# Sheet1.net
KiCad netlist of a schematic drawn in Altium Designer
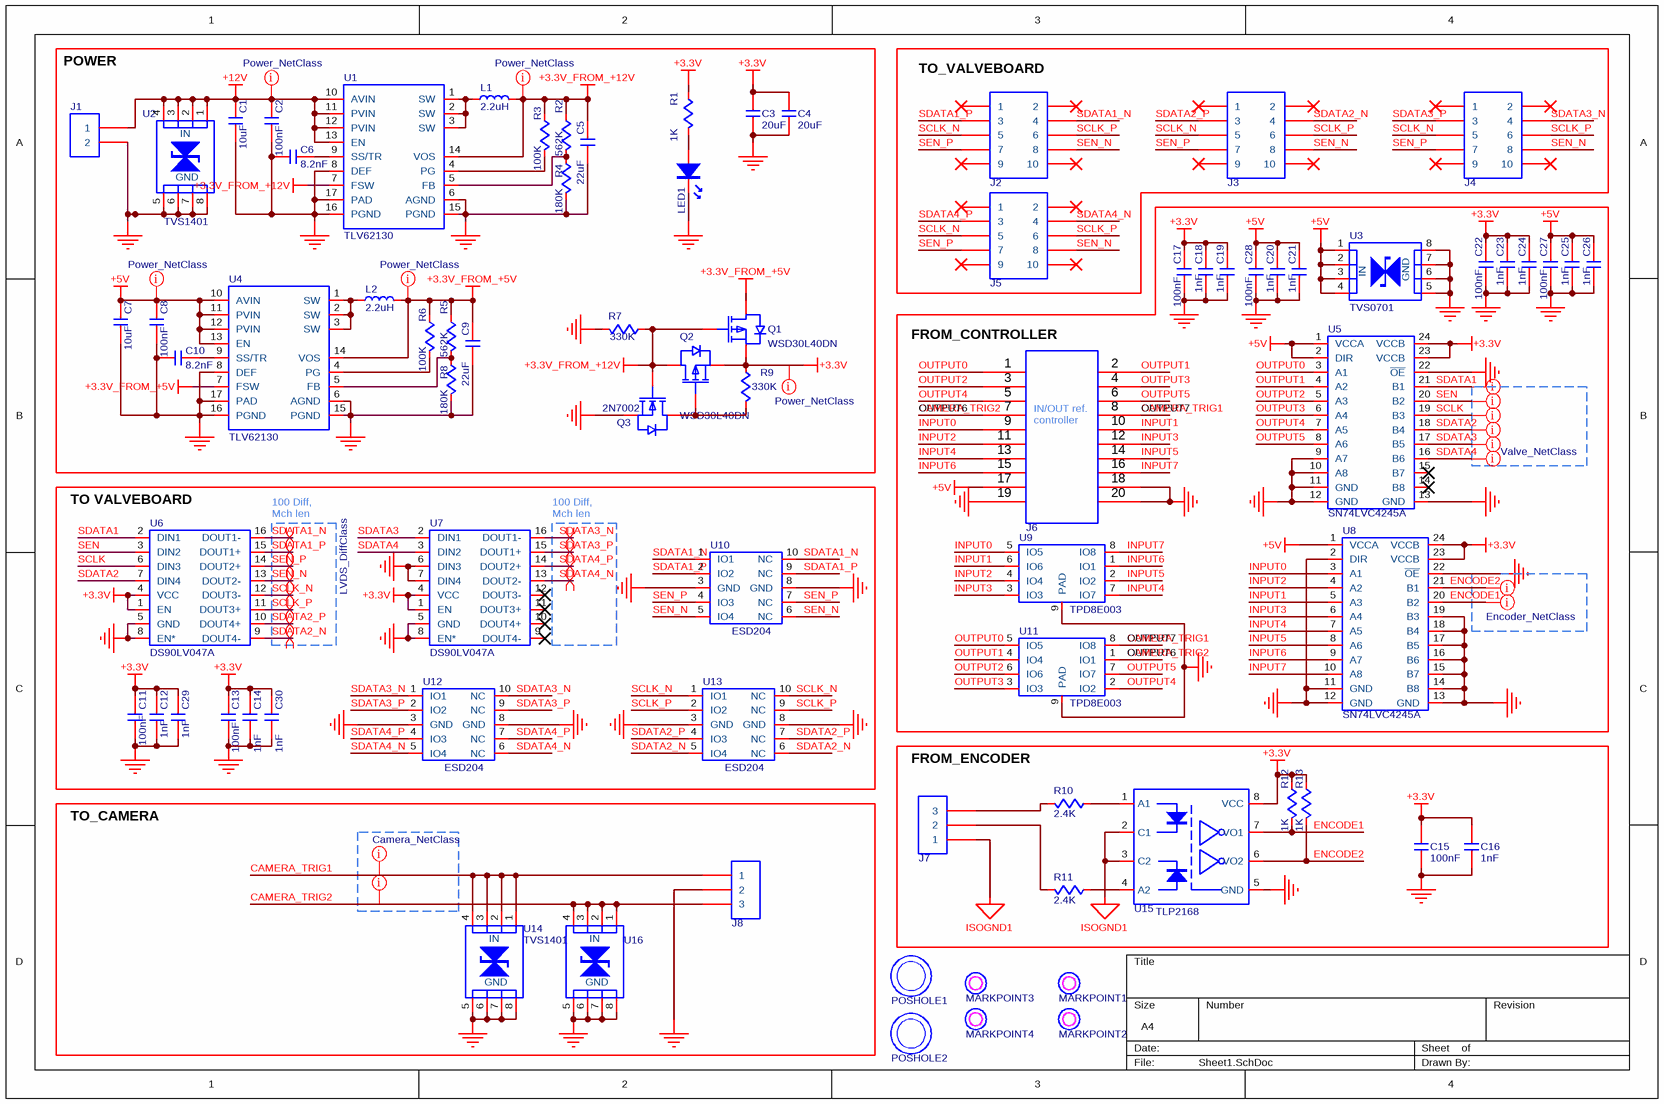
[diagram p0: Sheet1.SchDoc]

(export (version "E")
  (design (tool "Eeschema 10.0.6"))
  (components
    (comp (ref "C1")
      (value "10uF")
      (footprint "mw:C0805")
      (fields (field (name "VOLTAGE") "25V") (field (name "Comment") "C-NOMO"))
      (libsource (lib "mw") (part "C-NOMO"))
    )
    (comp (ref "C2")
      (value "100nF")
      (footprint "mw:C0402")
      (fields (field (name "VOLTAGE") "25V") (field (name "Comment") "C-NOMO"))
      (libsource (lib "mw") (part "C-NOMO"))
    )
    (comp (ref "C3")
      (value "20uF")
      (footprint "mw:C0805")
      (fields (field (name "VOLTAGE") "25V") (field (name "Comment") "C-NOMO"))
      (libsource (lib "mw") (part "C-NOMO"))
    )
    (comp (ref "C4")
      (value "20uF")
      (footprint "mw:C0805")
      (fields (field (name "VOLTAGE") "25V") (field (name "Comment") "C-NOMO"))
      (libsource (lib "mw") (part "C-NOMO"))
    )
    (comp (ref "C5")
      (value "22uF")
      (footprint "mw:C0805")
      (fields (field (name "VOLTAGE") "25V") (field (name "Comment") "C-NOMO"))
      (libsource (lib "mw") (part "C-NOMO"))
    )
    (comp (ref "C6")
      (value "8.2nF")
      (footprint "mw:C0402")
      (fields (field (name "VOLTAGE") "25V") (field (name "Comment") "C-NOMO"))
      (libsource (lib "mw") (part "C-NOMO"))
    )
    (comp (ref "C7")
      (value "10uF")
      (footprint "mw:C0805")
      (fields (field (name "VOLTAGE") "25V") (field (name "Comment") "C-NOMO"))
      (libsource (lib "mw") (part "C-NOMO"))
    )
    (comp (ref "C8")
      (value "100nF")
      (footprint "mw:C0402")
      (fields (field (name "VOLTAGE") "25V") (field (name "Comment") "C-NOMO"))
      (libsource (lib "mw") (part "C-NOMO"))
    )
    (comp (ref "C9")
      (value "22uF")
      (footprint "mw:C0805")
      (fields (field (name "VOLTAGE") "25V") (field (name "Comment") "C-NOMO"))
      (libsource (lib "mw") (part "C-NOMO"))
    )
    (comp (ref "C10")
      (value "8.2nF")
      (footprint "mw:C0402")
      (fields (field (name "VOLTAGE") "25V") (field (name "Comment") "C-NOMO"))
      (libsource (lib "mw") (part "C-NOMO"))
    )
    (comp (ref "C11")
      (value "100nF")
      (footprint "mw:C0402")
      (fields (field (name "VOLTAGE") "25V") (field (name "Comment") "C-NOMO"))
      (libsource (lib "mw") (part "C-NOMO"))
    )
    (comp (ref "C12")
      (value "1nF")
      (footprint "mw:C0402")
      (fields (field (name "VOLTAGE") "25V") (field (name "Comment") "C-NOMO"))
      (libsource (lib "mw") (part "C-NOMO"))
    )
    (comp (ref "C13")
      (value "100nF")
      (footprint "mw:C0402")
      (fields (field (name "VOLTAGE") "25V") (field (name "Comment") "C-NOMO"))
      (libsource (lib "mw") (part "C-NOMO"))
    )
    (comp (ref "C14")
      (value "1nF")
      (footprint "mw:C0402")
      (fields (field (name "VOLTAGE") "25V") (field (name "Comment") "C-NOMO"))
      (libsource (lib "mw") (part "C-NOMO"))
    )
    (comp (ref "C15")
      (value "100nF")
      (footprint "mw:C0402")
      (fields (field (name "VOLTAGE") "25V") (field (name "Comment") "C-NOMO"))
      (libsource (lib "mw") (part "C-NOMO"))
    )
    (comp (ref "C16")
      (value "1nF")
      (footprint "mw:C0402")
      (fields (field (name "VOLTAGE") "25V") (field (name "Comment") "C-NOMO"))
      (libsource (lib "mw") (part "C-NOMO"))
    )
    (comp (ref "C17")
      (value "100nF")
      (footprint "mw:C0402")
      (fields (field (name "VOLTAGE") "25V") (field (name "Comment") "C-NOMO"))
      (libsource (lib "mw") (part "C-NOMO"))
    )
    (comp (ref "C18")
      (value "1nF")
      (footprint "mw:C0402")
      (fields (field (name "VOLTAGE") "25V") (field (name "Comment") "C-NOMO"))
      (libsource (lib "mw") (part "C-NOMO"))
    )
    (comp (ref "C19")
      (value "1nF")
      (footprint "mw:C0402")
      (fields (field (name "VOLTAGE") "25V") (field (name "Comment") "C-NOMO"))
      (libsource (lib "mw") (part "C-NOMO"))
    )
    (comp (ref "C20")
      (value "1nF")
      (footprint "mw:C0402")
      (fields (field (name "VOLTAGE") "25V") (field (name "Comment") "C-NOMO"))
      (libsource (lib "mw") (part "C-NOMO"))
    )
    (comp (ref "C21")
      (value "1nF")
      (footprint "mw:C0402")
      (fields (field (name "VOLTAGE") "25V") (field (name "Comment") "C-NOMO"))
      (libsource (lib "mw") (part "C-NOMO"))
    )
    (comp (ref "C22")
      (value "100nF")
      (footprint "mw:C0402")
      (fields (field (name "VOLTAGE") "25V") (field (name "Comment") "C-NOMO"))
      (libsource (lib "mw") (part "C-NOMO"))
    )
    (comp (ref "C23")
      (value "1nF")
      (footprint "mw:C0402")
      (fields (field (name "VOLTAGE") "25V") (field (name "Comment") "C-NOMO"))
      (libsource (lib "mw") (part "C-NOMO"))
    )
    (comp (ref "C24")
      (value "1nF")
      (footprint "mw:C0402")
      (fields (field (name "VOLTAGE") "25V") (field (name "Comment") "C-NOMO"))
      (libsource (lib "mw") (part "C-NOMO"))
    )
    (comp (ref "C25")
      (value "1nF")
      (footprint "mw:C0402")
      (fields (field (name "VOLTAGE") "25V") (field (name "Comment") "C-NOMO"))
      (libsource (lib "mw") (part "C-NOMO"))
    )
    (comp (ref "C26")
      (value "1nF")
      (footprint "mw:C0402")
      (fields (field (name "VOLTAGE") "25V") (field (name "Comment") "C-NOMO"))
      (libsource (lib "mw") (part "C-NOMO"))
    )
    (comp (ref "C27")
      (value "100nF")
      (footprint "mw:C0402")
      (fields (field (name "VOLTAGE") "25V") (field (name "Comment") "C-NOMO"))
      (libsource (lib "mw") (part "C-NOMO"))
    )
    (comp (ref "C28")
      (value "100nF")
      (footprint "mw:C0402")
      (fields (field (name "VOLTAGE") "25V") (field (name "Comment") "C-NOMO"))
      (libsource (lib "mw") (part "C-NOMO"))
    )
    (comp (ref "C29")
      (value "1nF")
      (footprint "mw:C0402")
      (fields (field (name "VOLTAGE") "25V") (field (name "Comment") "C-NOMO"))
      (libsource (lib "mw") (part "C-NOMO"))
    )
    (comp (ref "C30")
      (value "1nF")
      (footprint "mw:C0402")
      (fields (field (name "VOLTAGE") "25V") (field (name "Comment") "C-NOMO"))
      (libsource (lib "mw") (part "C-NOMO"))
    )
    (comp (ref "J1") (value "HDR1X2") (footprint "mw:KF301-5.0-2P") (libsource (lib "mw") (part "HDR1X2")))
    (comp (ref "J2") (value "HDR2X5") (footprint "mw:HDR2X5-NJ") (libsource (lib "mw") (part "HDR2X5")))
    (comp (ref "J3") (value "HDR2X5") (footprint "mw:HDR2X5-NJ") (libsource (lib "mw") (part "HDR2X5")))
    (comp (ref "J4") (value "HDR2X5") (footprint "mw:HDR2X5-NJ") (libsource (lib "mw") (part "HDR2X5")))
    (comp (ref "J5") (value "HDR2X5") (footprint "mw:HDR2X5-NJ") (libsource (lib "mw") (part "HDR2X5")))
    (comp (ref "J6") (value "HDR2X10") (footprint "mw:HDR2X10-NJ") (libsource (lib "mw") (part "HDR2X10")))
    (comp (ref "J7") (value "HDR1X3") (footprint "mw:KF301-5.0-3P") (libsource (lib "mw") (part "HDR1X3")))
    (comp (ref "J8") (value "HDR1X3") (footprint "mw:KF301-5.0-3P") (libsource (lib "") (part "HDR1X3_1")))
    (comp (ref "L1")
      (value "2.2uH")
      (footprint "mw:FXL0624")
      (fields (field (name "Comment") "L") (field (name "PUBLISHER") "Altium Limited"))
      (libsource (lib "mw") (part "L"))
    )
    (comp (ref "L2")
      (value "2.2uH")
      (footprint "mw:FXL0624")
      (fields (field (name "Comment") "L") (field (name "PUBLISHER") "Altium Limited"))
      (libsource (lib "mw") (part "L"))
    )
    (comp (ref "LED1") (value "LED") (footprint "mw:LED0603") (libsource (lib "mw") (part "LED")))
    (comp (ref "MARKPOINT1")
      (value "MARKPOINT")
      (footprint "mw:MARKPOINT-1.0")
      (libsource (lib "mw") (part "MARKPOINT"))
    )
    (comp (ref "MARKPOINT2")
      (value "MARKPOINT")
      (footprint "mw:MARKPOINT-1.0")
      (libsource (lib "mw") (part "MARKPOINT"))
    )
    (comp (ref "MARKPOINT3")
      (value "MARKPOINT")
      (footprint "mw:MARKPOINT-1.0")
      (libsource (lib "mw") (part "MARKPOINT"))
    )
    (comp (ref "MARKPOINT4")
      (value "MARKPOINT")
      (footprint "mw:MARKPOINT-1.0")
      (libsource (lib "mw") (part "MARKPOINT"))
    )
    (comp (ref "POSHOLE1")
      (value "POSHOLE")
      (footprint "mw:POSHOLE-3.2")
      (libsource (lib "mw") (part "POSHOLE"))
    )
    (comp (ref "POSHOLE2")
      (value "POSHOLE")
      (footprint "mw:POSHOLE-3.2")
      (libsource (lib "mw") (part "POSHOLE"))
    )
    (comp (ref "Q1")
      (value "WSD30L40DN")
      (footprint "mw:WSD30L40DN")
      (libsource (lib "mw") (part "WSD30L40DN"))
    )
    (comp (ref "Q2")
      (value "WSD30L40DN")
      (footprint "mw:WSD30L40DN")
      (libsource (lib "mw") (part "WSD30L40DN"))
    )
    (comp (ref "Q3") (value "2N7002") (footprint "mw:2N7002") (libsource (lib "mw") (part "2N7002")))
    (comp (ref "R1")
      (value "1K")
      (footprint "mw:R0402")
      (fields (field (name "Comment") "R"))
      (libsource (lib "mw") (part "R"))
    )
    (comp (ref "R2")
      (value "562K")
      (footprint "mw:R0402")
      (fields (field (name "Comment") "R"))
      (libsource (lib "mw") (part "R"))
    )
    (comp (ref "R3")
      (value "100K")
      (footprint "mw:R0402")
      (fields (field (name "Comment") "R"))
      (libsource (lib "mw") (part "R"))
    )
    (comp (ref "R4")
      (value "180K")
      (footprint "mw:R0402")
      (fields (field (name "Comment") "R"))
      (libsource (lib "mw") (part "R"))
    )
    (comp (ref "R5")
      (value "562K")
      (footprint "mw:R0402")
      (fields (field (name "Comment") "R"))
      (libsource (lib "mw") (part "R"))
    )
    (comp (ref "R6")
      (value "100K")
      (footprint "mw:R0402")
      (fields (field (name "Comment") "R"))
      (libsource (lib "mw") (part "R"))
    )
    (comp (ref "R7")
      (value "330K")
      (footprint "mw:R0402")
      (fields (field (name "Comment") "R"))
      (libsource (lib "mw") (part "R"))
    )
    (comp (ref "R8")
      (value "180K")
      (footprint "mw:R0402")
      (fields (field (name "Comment") "R"))
      (libsource (lib "mw") (part "R"))
    )
    (comp (ref "R9")
      (value "330K")
      (footprint "mw:R0402")
      (fields (field (name "Comment") "R"))
      (libsource (lib "mw") (part "R"))
    )
    (comp (ref "R10")
      (value "2.4K")
      (footprint "mw:R2512")
      (fields (field (name "Comment") "R"))
      (libsource (lib "mw") (part "R"))
    )
    (comp (ref "R11")
      (value "2.4K")
      (footprint "mw:R2512")
      (fields (field (name "Comment") "R"))
      (libsource (lib "mw") (part "R"))
    )
    (comp (ref "R12")
      (value "1K")
      (footprint "mw:R0402")
      (fields (field (name "Comment") "R"))
      (libsource (lib "mw") (part "R"))
    )
    (comp (ref "R13")
      (value "1K")
      (footprint "mw:R0402")
      (fields (field (name "Comment") "R"))
      (libsource (lib "mw") (part "R"))
    )
    (comp (ref "U1") (value "TLV62130") (footprint "mw:TLV62130") (libsource (lib "mw") (part "TLV62130")))
    (comp (ref "U2") (value "TVS1401") (footprint "mw:TVS1401") (libsource (lib "mw") (part "TVS1401")))
    (comp (ref "U3") (value "TVS0701") (footprint "mw:TVS0701") (libsource (lib "mw") (part "TVS0701")))
    (comp (ref "U4") (value "TLV62130") (footprint "mw:TLV62130") (libsource (lib "mw") (part "TLV62130")))
    (comp (ref "U5")
      (value "SN74LVC4245A")
      (footprint "mw:SN74LVC4245A")
      (libsource (lib "mw") (part "SN74LVC4245A"))
    )
    (comp (ref "U6")
      (value "DS90LV047A")
      (footprint "mw:DS90LV047")
      (libsource (lib "mw") (part "DS90LV047A"))
    )
    (comp (ref "U7")
      (value "DS90LV047A")
      (footprint "mw:DS90LV047")
      (libsource (lib "mw") (part "DS90LV047A"))
    )
    (comp (ref "U8")
      (value "SN74LVC4245A")
      (footprint "mw:SN74LVC4245A")
      (libsource (lib "mw") (part "SN74LVC4245A"))
    )
    (comp (ref "U9") (value "TPD8E003") (footprint "mw:TPD8E003") (libsource (lib "") (part "TPD8E003_1")))
    (comp (ref "U10") (value "ESD204") (footprint "mw:ESD204") (libsource (lib "mw") (part "ESD204")))
    (comp (ref "U11") (value "TPD8E003") (footprint "mw:TPD8E003") (libsource (lib "mw") (part "TPD8E003")))
    (comp (ref "U12") (value "ESD204") (footprint "mw:ESD204") (libsource (lib "mw") (part "ESD204")))
    (comp (ref "U13") (value "ESD204") (footprint "mw:ESD204") (libsource (lib "mw") (part "ESD204")))
    (comp (ref "U14") (value "TVS1401") (footprint "mw:TVS1401") (libsource (lib "mw") (part "TVS1401")))
    (comp (ref "U15") (value "TLP2168") (footprint "TLP2168") (libsource (lib "mw") (part "TLP2168")))
    (comp (ref "U16") (value "TVS1401") (footprint "mw:TVS1401") (libsource (lib "mw") (part "TVS1401")))
  )
  (nets
    (net (code "1") (name "+3.3V") (class "Default")
      (node (ref "C11") (pin "2") (pinfunction "2_2") (pintype "passive"))
      (node (ref "C12") (pin "2") (pinfunction "2_2") (pintype "passive"))
      (node (ref "C13") (pin "2") (pinfunction "2_2") (pintype "passive"))
      (node (ref "C14") (pin "2") (pinfunction "2_2") (pintype "passive"))
      (node (ref "C15") (pin "2") (pinfunction "2_2") (pintype "passive"))
      (node (ref "C16") (pin "2") (pinfunction "2_2") (pintype "passive"))
      (node (ref "C17") (pin "2") (pinfunction "2_2") (pintype "passive"))
      (node (ref "C18") (pin "2") (pinfunction "2_2") (pintype "passive"))
      (node (ref "C19") (pin "2") (pinfunction "2_2") (pintype "passive"))
      (node (ref "C22") (pin "2") (pinfunction "2_2") (pintype "passive"))
      (node (ref "C23") (pin "2") (pinfunction "2_2") (pintype "passive"))
      (node (ref "C24") (pin "2") (pinfunction "2_2") (pintype "passive"))
      (node (ref "C29") (pin "2") (pinfunction "2_2") (pintype "passive"))
      (node (ref "C3") (pin "2") (pinfunction "2_2") (pintype "passive"))
      (node (ref "C30") (pin "2") (pinfunction "2_2") (pintype "passive"))
      (node (ref "C4") (pin "2") (pinfunction "2_2") (pintype "passive"))
      (node (ref "Q1") (pin "S") (pinfunction "S_S") (pintype "passive"))
      (node (ref "Q2") (pin "S") (pinfunction "S_S") (pintype "passive"))
      (node (ref "R1") (pin "2") (pinfunction "2_2") (pintype "passive"))
      (node (ref "R12") (pin "2") (pinfunction "2_2") (pintype "passive"))
      (node (ref "R13") (pin "2") (pinfunction "2_2") (pintype "passive"))
      (node (ref "R9") (pin "2") (pinfunction "2_2") (pintype "passive"))
      (node (ref "U15") (pin "8") (pinfunction "VCC_8") (pintype "passive"))
      (node (ref "U5") (pin "23") (pinfunction "VCCB_23") (pintype "passive"))
      (node (ref "U5") (pin "24") (pinfunction "VCCB_24") (pintype "passive"))
      (node (ref "U6") (pin "1") (pinfunction "EN_1") (pintype "passive"))
      (node (ref "U6") (pin "4") (pinfunction "VCC_4") (pintype "passive"))
      (node (ref "U7") (pin "1") (pinfunction "EN_1") (pintype "passive"))
      (node (ref "U7") (pin "4") (pinfunction "VCC_4") (pintype "passive"))
      (node (ref "U8") (pin "23") (pinfunction "VCCB_23") (pintype "passive"))
      (node (ref "U8") (pin "24") (pinfunction "VCCB_24") (pintype "passive"))
    )
    (net (code "2") (name "+3.3V_FROM_+5V") (class "Default")
      (node (ref "C9") (pin "1") (pinfunction "1_1") (pintype "passive"))
      (node (ref "L2") (pin "2") (pinfunction "2_2") (pintype "passive"))
      (node (ref "Q1") (pin "D") (pinfunction "D_D") (pintype "passive"))
      (node (ref "R5") (pin "2") (pinfunction "2_2") (pintype "passive"))
      (node (ref "R6") (pin "2") (pinfunction "2_2") (pintype "passive"))
      (node (ref "U4") (pin "14") (pinfunction "VOS_14") (pintype "passive"))
      (node (ref "U4") (pin "7") (pinfunction "FSW_7") (pintype "passive"))
    )
    (net (code "3") (name "+3.3V_FROM_+12V") (class "Default")
      (node (ref "C5") (pin "1") (pinfunction "1_1") (pintype "passive"))
      (node (ref "L1") (pin "2") (pinfunction "2_2") (pintype "passive"))
      (node (ref "Q1") (pin "G") (pinfunction "G_G") (pintype "passive"))
      (node (ref "Q2") (pin "D") (pinfunction "D_D") (pintype "passive"))
      (node (ref "Q3") (pin "G") (pinfunction "G_G") (pintype "passive"))
      (node (ref "R2") (pin "2") (pinfunction "2_2") (pintype "passive"))
      (node (ref "R3") (pin "2") (pinfunction "2_2") (pintype "passive"))
      (node (ref "R7") (pin "2") (pinfunction "2_2") (pintype "passive"))
      (node (ref "U1") (pin "14") (pinfunction "VOS_14") (pintype "passive"))
      (node (ref "U1") (pin "7") (pinfunction "FSW_7") (pintype "passive"))
    )
    (net (code "4") (name "+5V") (class "Default")
      (node (ref "C20") (pin "2") (pinfunction "2_2") (pintype "passive"))
      (node (ref "C21") (pin "2") (pinfunction "2_2") (pintype "passive"))
      (node (ref "C25") (pin "2") (pinfunction "2_2") (pintype "passive"))
      (node (ref "C26") (pin "2") (pinfunction "2_2") (pintype "passive"))
      (node (ref "C27") (pin "2") (pinfunction "2_2") (pintype "passive"))
      (node (ref "C28") (pin "2") (pinfunction "2_2") (pintype "passive"))
      (node (ref "C7") (pin "2") (pinfunction "2_2") (pintype "passive"))
      (node (ref "C8") (pin "2") (pinfunction "2_2") (pintype "passive"))
      (node (ref "J6") (pin "17") (pintype "passive"))
      (node (ref "U3") (pin "1") (pinfunction "IN_1") (pintype "passive"))
      (node (ref "U3") (pin "2") (pinfunction "IN_2") (pintype "passive"))
      (node (ref "U3") (pin "3") (pinfunction "IN_3") (pintype "passive"))
      (node (ref "U3") (pin "4") (pinfunction "IN_4") (pintype "passive"))
      (node (ref "U4") (pin "10") (pinfunction "AVIN_10") (pintype "passive"))
      (node (ref "U4") (pin "11") (pinfunction "PVIN_11") (pintype "passive"))
      (node (ref "U4") (pin "12") (pinfunction "PVIN_12") (pintype "passive"))
      (node (ref "U4") (pin "13") (pinfunction "EN_13") (pintype "passive"))
      (node (ref "U5") (pin "1") (pinfunction "VCCA_1") (pintype "passive"))
      (node (ref "U5") (pin "2") (pinfunction "DIR_2") (pintype "passive"))
      (node (ref "U8") (pin "1") (pinfunction "VCCA_1") (pintype "passive"))
    )
    (net (code "5") (name "+12V") (class "Default")
      (node (ref "C1") (pin "2") (pinfunction "2_2") (pintype "passive"))
      (node (ref "C2") (pin "2") (pinfunction "2_2") (pintype "passive"))
      (node (ref "J1") (pin "1") (pinfunction "1_1") (pintype "passive"))
      (node (ref "U1") (pin "10") (pinfunction "AVIN_10") (pintype "passive"))
      (node (ref "U1") (pin "11") (pinfunction "PVIN_11") (pintype "passive"))
      (node (ref "U1") (pin "12") (pinfunction "PVIN_12") (pintype "passive"))
      (node (ref "U1") (pin "13") (pinfunction "EN_13") (pintype "passive"))
      (node (ref "U2") (pin "1") (pinfunction "IN_1") (pintype "passive"))
      (node (ref "U2") (pin "2") (pinfunction "IN_2") (pintype "passive"))
      (node (ref "U2") (pin "3") (pinfunction "IN_3") (pintype "passive"))
      (node (ref "U2") (pin "4") (pinfunction "IN_4") (pintype "passive"))
    )
    (net (code "6") (name "/CAMERA_TRIG1") (class "Default")
      (node (ref "J6") (pin "8") (pintype "passive"))
      (node (ref "J8") (pin "1") (pinfunction "1_1") (pintype "passive"))
      (node (ref "U11") (pin "8") (pinfunction "IO8_8") (pintype "passive"))
      (node (ref "U14") (pin "1") (pinfunction "IN_1") (pintype "passive"))
      (node (ref "U14") (pin "2") (pinfunction "IN_2") (pintype "passive"))
      (node (ref "U14") (pin "3") (pinfunction "IN_3") (pintype "passive"))
      (node (ref "U14") (pin "4") (pinfunction "IN_4") (pintype "passive"))
    )
    (net (code "7") (name "/CAMERA_TRIG2") (class "Default")
      (node (ref "J6") (pin "7") (pintype "passive"))
      (node (ref "J8") (pin "3") (pinfunction "3_3") (pintype "passive"))
      (node (ref "U11") (pin "1") (pinfunction "IO1_1") (pintype "passive"))
      (node (ref "U16") (pin "1") (pinfunction "IN_1") (pintype "passive"))
      (node (ref "U16") (pin "2") (pinfunction "IN_2") (pintype "passive"))
      (node (ref "U16") (pin "3") (pinfunction "IN_3") (pintype "passive"))
      (node (ref "U16") (pin "4") (pinfunction "IN_4") (pintype "passive"))
    )
    (net (code "8") (name "/ENCODE1") (class "Default")
      (node (ref "R12") (pin "1") (pinfunction "1_1") (pintype "passive"))
      (node (ref "U15") (pin "7") (pinfunction "VO1_7") (pintype "passive"))
      (node (ref "U8") (pin "20") (pinfunction "B2_20") (pintype "passive"))
    )
    (net (code "9") (name "/ENCODE2") (class "Default")
      (node (ref "R13") (pin "1") (pinfunction "1_1") (pintype "passive"))
      (node (ref "U15") (pin "6") (pinfunction "VO2_6") (pintype "passive"))
      (node (ref "U8") (pin "21") (pinfunction "B1_21") (pintype "passive"))
    )
    (net (code "10") (name "/INPUT0") (class "Default")
      (node (ref "J6") (pin "9") (pintype "passive"))
      (node (ref "U8") (pin "3") (pinfunction "A1_3") (pintype "passive"))
      (node (ref "U9") (pin "5") (pinfunction "IO5_5") (pintype "passive"))
    )
    (net (code "11") (name "/INPUT1") (class "Default")
      (node (ref "J6") (pin "10") (pintype "passive"))
      (node (ref "U8") (pin "5") (pinfunction "A3_5") (pintype "passive"))
      (node (ref "U9") (pin "6") (pinfunction "IO6_6") (pintype "passive"))
    )
    (net (code "12") (name "/INPUT2") (class "Default")
      (node (ref "J6") (pin "11") (pintype "passive"))
      (node (ref "U8") (pin "4") (pinfunction "A2_4") (pintype "passive"))
      (node (ref "U9") (pin "4") (pinfunction "IO4_4") (pintype "passive"))
    )
    (net (code "13") (name "/INPUT3") (class "Default")
      (node (ref "J6") (pin "12") (pintype "passive"))
      (node (ref "U8") (pin "6") (pinfunction "A4_6") (pintype "passive"))
      (node (ref "U9") (pin "3") (pinfunction "IO3_3") (pintype "passive"))
    )
    (net (code "14") (name "/INPUT4") (class "Default")
      (node (ref "J6") (pin "13") (pintype "passive"))
      (node (ref "U8") (pin "7") (pinfunction "A5_7") (pintype "passive"))
      (node (ref "U9") (pin "7") (pinfunction "IO7_7") (pintype "passive"))
    )
    (net (code "15") (name "/INPUT5") (class "Default")
      (node (ref "J6") (pin "14") (pintype "passive"))
      (node (ref "U8") (pin "8") (pinfunction "A6_8") (pintype "passive"))
      (node (ref "U9") (pin "2") (pinfunction "IO2_2") (pintype "passive"))
    )
    (net (code "16") (name "/INPUT6") (class "Default")
      (node (ref "J6") (pin "15") (pintype "passive"))
      (node (ref "U8") (pin "9") (pinfunction "A7_9") (pintype "passive"))
      (node (ref "U9") (pin "1") (pinfunction "IO1_1") (pintype "passive"))
    )
    (net (code "17") (name "/INPUT7") (class "Default")
      (node (ref "J6") (pin "16") (pintype "passive"))
      (node (ref "U8") (pin "10") (pinfunction "A8_10") (pintype "passive"))
      (node (ref "U9") (pin "8") (pinfunction "IO8_8") (pintype "passive"))
    )
    (net (code "18") (name "/OUTPUT0") (class "Default")
      (node (ref "J6") (pin "1") (pintype "passive"))
      (node (ref "U11") (pin "5") (pinfunction "IO5_5") (pintype "passive"))
      (node (ref "U5") (pin "3") (pinfunction "A1_3") (pintype "passive"))
    )
    (net (code "19") (name "/OUTPUT1") (class "Default")
      (node (ref "J6") (pin "2") (pintype "passive"))
      (node (ref "U11") (pin "4") (pinfunction "IO4_4") (pintype "passive"))
      (node (ref "U5") (pin "4") (pinfunction "A2_4") (pintype "passive"))
    )
    (net (code "20") (name "/OUTPUT2") (class "Default")
      (node (ref "J6") (pin "3") (pintype "passive"))
      (node (ref "U11") (pin "6") (pinfunction "IO6_6") (pintype "passive"))
      (node (ref "U5") (pin "5") (pinfunction "A3_5") (pintype "passive"))
    )
    (net (code "21") (name "/OUTPUT3") (class "Default")
      (node (ref "J6") (pin "4") (pintype "passive"))
      (node (ref "U11") (pin "3") (pinfunction "IO3_3") (pintype "passive"))
      (node (ref "U5") (pin "6") (pinfunction "A4_6") (pintype "passive"))
    )
    (net (code "22") (name "/OUTPUT4") (class "Default")
      (node (ref "J6") (pin "5") (pintype "passive"))
      (node (ref "U11") (pin "2") (pinfunction "IO2_2") (pintype "passive"))
      (node (ref "U5") (pin "7") (pinfunction "A5_7") (pintype "passive"))
    )
    (net (code "23") (name "/OUTPUT5") (class "Default")
      (node (ref "J6") (pin "6") (pintype "passive"))
      (node (ref "U11") (pin "7") (pinfunction "IO7_7") (pintype "passive"))
      (node (ref "U5") (pin "8") (pinfunction "A6_8") (pintype "passive"))
    )
    (net (code "24") (name "/SCLK") (class "Default")
      (node (ref "U5") (pin "19") (pinfunction "B3_19") (pintype "passive"))
      (node (ref "U6") (pin "6") (pinfunction "DIN3_6") (pintype "passive"))
    )
    (net (code "25") (name "/SCLK_N") (class "Default")
      (node (ref "J2") (pin "5") (pinfunction "5_5") (pintype "passive"))
      (node (ref "J3") (pin "5") (pinfunction "5_5") (pintype "passive"))
      (node (ref "J4") (pin "5") (pinfunction "5_5") (pintype "passive"))
      (node (ref "J5") (pin "5") (pinfunction "5_5") (pintype "passive"))
      (node (ref "U13") (pin "1") (pinfunction "IO1_1") (pintype "passive"))
      (node (ref "U13") (pin "10") (pinfunction "NC_10") (pintype "passive"))
      (node (ref "U6") (pin "12") (pinfunction "DOUT3-_12") (pintype "passive"))
    )
    (net (code "26") (name "/SCLK_P") (class "Default")
      (node (ref "J2") (pin "6") (pinfunction "6_6") (pintype "passive"))
      (node (ref "J3") (pin "6") (pinfunction "6_6") (pintype "passive"))
      (node (ref "J4") (pin "6") (pinfunction "6_6") (pintype "passive"))
      (node (ref "J5") (pin "6") (pinfunction "6_6") (pintype "passive"))
      (node (ref "U13") (pin "2") (pinfunction "IO2_2") (pintype "passive"))
      (node (ref "U13") (pin "9") (pinfunction "NC_9") (pintype "passive"))
      (node (ref "U6") (pin "11") (pinfunction "DOUT3+_11") (pintype "passive"))
    )
    (net (code "27") (name "/SDATA1") (class "Default")
      (node (ref "U5") (pin "21") (pinfunction "B1_21") (pintype "passive"))
      (node (ref "U6") (pin "2") (pinfunction "DIN1_2") (pintype "passive"))
    )
    (net (code "28") (name "/SDATA1_N") (class "Default")
      (node (ref "J2") (pin "4") (pinfunction "4_4") (pintype "passive"))
      (node (ref "U10") (pin "1") (pinfunction "IO1_1") (pintype "passive"))
      (node (ref "U10") (pin "10") (pinfunction "NC_10") (pintype "passive"))
      (node (ref "U6") (pin "16") (pinfunction "DOUT1-_16") (pintype "passive"))
    )
    (net (code "29") (name "/SDATA1_P") (class "Default")
      (node (ref "J2") (pin "3") (pinfunction "3_3") (pintype "passive"))
      (node (ref "U10") (pin "2") (pinfunction "IO2_2") (pintype "passive"))
      (node (ref "U10") (pin "9") (pinfunction "NC_9") (pintype "passive"))
      (node (ref "U6") (pin "15") (pinfunction "DOUT1+_15") (pintype "passive"))
    )
    (net (code "30") (name "/SDATA2") (class "Default")
      (node (ref "U5") (pin "18") (pinfunction "B4_18") (pintype "passive"))
      (node (ref "U6") (pin "7") (pinfunction "DIN4_7") (pintype "passive"))
    )
    (net (code "31") (name "/SDATA2_N") (class "Default")
      (node (ref "J3") (pin "4") (pinfunction "4_4") (pintype "passive"))
      (node (ref "U13") (pin "5") (pinfunction "IO4_5") (pintype "passive"))
      (node (ref "U13") (pin "6") (pinfunction "NC_6") (pintype "passive"))
      (node (ref "U6") (pin "9") (pinfunction "DOUT4-_9") (pintype "passive"))
    )
    (net (code "32") (name "/SDATA2_P") (class "Default")
      (node (ref "J3") (pin "3") (pinfunction "3_3") (pintype "passive"))
      (node (ref "U13") (pin "4") (pinfunction "IO3_4") (pintype "passive"))
      (node (ref "U13") (pin "7") (pinfunction "NC_7") (pintype "passive"))
      (node (ref "U6") (pin "10") (pinfunction "DOUT4+_10") (pintype "passive"))
    )
    (net (code "33") (name "/SDATA3") (class "Default")
      (node (ref "U5") (pin "17") (pinfunction "B5_17") (pintype "passive"))
      (node (ref "U7") (pin "2") (pinfunction "DIN1_2") (pintype "passive"))
    )
    (net (code "34") (name "/SDATA3_N") (class "Default")
      (node (ref "J4") (pin "4") (pinfunction "4_4") (pintype "passive"))
      (node (ref "U12") (pin "1") (pinfunction "IO1_1") (pintype "passive"))
      (node (ref "U12") (pin "10") (pinfunction "NC_10") (pintype "passive"))
      (node (ref "U7") (pin "16") (pinfunction "DOUT1-_16") (pintype "passive"))
    )
    (net (code "35") (name "/SDATA3_P") (class "Default")
      (node (ref "J4") (pin "3") (pinfunction "3_3") (pintype "passive"))
      (node (ref "U12") (pin "2") (pinfunction "IO2_2") (pintype "passive"))
      (node (ref "U12") (pin "9") (pinfunction "NC_9") (pintype "passive"))
      (node (ref "U7") (pin "15") (pinfunction "DOUT1+_15") (pintype "passive"))
    )
    (net (code "36") (name "/SDATA4") (class "Default")
      (node (ref "U5") (pin "16") (pinfunction "B6_16") (pintype "passive"))
      (node (ref "U7") (pin "3") (pinfunction "DIN2_3") (pintype "passive"))
    )
    (net (code "37") (name "/SDATA4_N") (class "Default")
      (node (ref "J5") (pin "4") (pinfunction "4_4") (pintype "passive"))
      (node (ref "U12") (pin "5") (pinfunction "IO4_5") (pintype "passive"))
      (node (ref "U12") (pin "6") (pinfunction "NC_6") (pintype "passive"))
      (node (ref "U7") (pin "13") (pinfunction "DOUT2-_13") (pintype "passive"))
    )
    (net (code "38") (name "/SDATA4_P") (class "Default")
      (node (ref "J5") (pin "3") (pinfunction "3_3") (pintype "passive"))
      (node (ref "U12") (pin "4") (pinfunction "IO3_4") (pintype "passive"))
      (node (ref "U12") (pin "7") (pinfunction "NC_7") (pintype "passive"))
      (node (ref "U7") (pin "14") (pinfunction "DOUT2+_14") (pintype "passive"))
    )
    (net (code "39") (name "/SEN") (class "Default")
      (node (ref "U5") (pin "20") (pinfunction "B2_20") (pintype "passive"))
      (node (ref "U6") (pin "3") (pinfunction "DIN2_3") (pintype "passive"))
    )
    (net (code "40") (name "/SEN_N") (class "Default")
      (node (ref "J2") (pin "8") (pinfunction "8_8") (pintype "passive"))
      (node (ref "J3") (pin "8") (pinfunction "8_8") (pintype "passive"))
      (node (ref "J4") (pin "8") (pinfunction "8_8") (pintype "passive"))
      (node (ref "J5") (pin "8") (pinfunction "8_8") (pintype "passive"))
      (node (ref "U10") (pin "5") (pinfunction "IO4_5") (pintype "passive"))
      (node (ref "U10") (pin "6") (pinfunction "NC_6") (pintype "passive"))
      (node (ref "U6") (pin "13") (pinfunction "DOUT2-_13") (pintype "passive"))
    )
    (net (code "41") (name "/SEN_P") (class "Default")
      (node (ref "J2") (pin "7") (pinfunction "7_7") (pintype "passive"))
      (node (ref "J3") (pin "7") (pinfunction "7_7") (pintype "passive"))
      (node (ref "J4") (pin "7") (pinfunction "7_7") (pintype "passive"))
      (node (ref "J5") (pin "7") (pinfunction "7_7") (pintype "passive"))
      (node (ref "U10") (pin "4") (pinfunction "IO3_4") (pintype "passive"))
      (node (ref "U10") (pin "7") (pinfunction "NC_7") (pintype "passive"))
      (node (ref "U6") (pin "14") (pinfunction "DOUT2+_14") (pintype "passive"))
    )
    (net (code "42") (name "DGND") (class "Default")
      (node (ref "C1") (pin "1") (pinfunction "1_1") (pintype "passive"))
      (node (ref "C10") (pin "2") (pinfunction "2_2") (pintype "passive"))
      (node (ref "C11") (pin "1") (pinfunction "1_1") (pintype "passive"))
      (node (ref "C12") (pin "1") (pinfunction "1_1") (pintype "passive"))
      (node (ref "C13") (pin "1") (pinfunction "1_1") (pintype "passive"))
      (node (ref "C14") (pin "1") (pinfunction "1_1") (pintype "passive"))
      (node (ref "C15") (pin "1") (pinfunction "1_1") (pintype "passive"))
      (node (ref "C16") (pin "1") (pinfunction "1_1") (pintype "passive"))
      (node (ref "C17") (pin "1") (pinfunction "1_1") (pintype "passive"))
      (node (ref "C18") (pin "1") (pinfunction "1_1") (pintype "passive"))
      (node (ref "C19") (pin "1") (pinfunction "1_1") (pintype "passive"))
      (node (ref "C2") (pin "1") (pinfunction "1_1") (pintype "passive"))
      (node (ref "C20") (pin "1") (pinfunction "1_1") (pintype "passive"))
      (node (ref "C21") (pin "1") (pinfunction "1_1") (pintype "passive"))
      (node (ref "C22") (pin "1") (pinfunction "1_1") (pintype "passive"))
      (node (ref "C23") (pin "1") (pinfunction "1_1") (pintype "passive"))
      (node (ref "C24") (pin "1") (pinfunction "1_1") (pintype "passive"))
      (node (ref "C25") (pin "1") (pinfunction "1_1") (pintype "passive"))
      (node (ref "C26") (pin "1") (pinfunction "1_1") (pintype "passive"))
      (node (ref "C27") (pin "1") (pinfunction "1_1") (pintype "passive"))
      (node (ref "C28") (pin "1") (pinfunction "1_1") (pintype "passive"))
      (node (ref "C29") (pin "1") (pinfunction "1_1") (pintype "passive"))
      (node (ref "C3") (pin "1") (pinfunction "1_1") (pintype "passive"))
      (node (ref "C30") (pin "1") (pinfunction "1_1") (pintype "passive"))
      (node (ref "C4") (pin "1") (pinfunction "1_1") (pintype "passive"))
      (node (ref "C5") (pin "2") (pinfunction "2_2") (pintype "passive"))
      (node (ref "C6") (pin "2") (pinfunction "2_2") (pintype "passive"))
      (node (ref "C7") (pin "1") (pinfunction "1_1") (pintype "passive"))
      (node (ref "C8") (pin "1") (pinfunction "1_1") (pintype "passive"))
      (node (ref "C9") (pin "2") (pinfunction "2_2") (pintype "passive"))
      (node (ref "J1") (pin "2") (pinfunction "2_2") (pintype "passive"))
      (node (ref "J6") (pin "18") (pintype "passive"))
      (node (ref "J6") (pin "19") (pintype "passive"))
      (node (ref "J6") (pin "20") (pintype "passive"))
      (node (ref "J8") (pin "2") (pinfunction "2_2") (pintype "passive"))
      (node (ref "LED1") (pin "1") (pinfunction "1_1") (pintype "passive"))
      (node (ref "Q3") (pin "S") (pinfunction "S_S") (pintype "passive"))
      (node (ref "R4") (pin "1") (pinfunction "1_1") (pintype "passive"))
      (node (ref "R7") (pin "1") (pinfunction "1_1") (pintype "passive"))
      (node (ref "R8") (pin "1") (pinfunction "1_1") (pintype "passive"))
      (node (ref "U1") (pin "15") (pinfunction "PGND_15") (pintype "passive"))
      (node (ref "U1") (pin "16") (pinfunction "PGND_16") (pintype "passive"))
      (node (ref "U1") (pin "17") (pinfunction "PAD_17") (pintype "passive"))
      (node (ref "U1") (pin "6") (pinfunction "AGND_6") (pintype "passive"))
      (node (ref "U1") (pin "8") (pinfunction "DEF_8") (pintype "passive"))
      (node (ref "U10") (pin "3") (pinfunction "GND_3") (pintype "passive"))
      (node (ref "U10") (pin "8") (pinfunction "GND_8") (pintype "passive"))
      (node (ref "U11") (pin "9") (pinfunction "PAD_9") (pintype "passive"))
      (node (ref "U12") (pin "3") (pinfunction "GND_3") (pintype "passive"))
      (node (ref "U12") (pin "8") (pinfunction "GND_8") (pintype "passive"))
      (node (ref "U13") (pin "3") (pinfunction "GND_3") (pintype "passive"))
      (node (ref "U13") (pin "8") (pinfunction "GND_8") (pintype "passive"))
      (node (ref "U14") (pin "5") (pinfunction "GND_5") (pintype "passive"))
      (node (ref "U14") (pin "6") (pinfunction "GND_6") (pintype "passive"))
      (node (ref "U14") (pin "7") (pinfunction "GND_7") (pintype "passive"))
      (node (ref "U14") (pin "8") (pinfunction "GND_8") (pintype "passive"))
      (node (ref "U15") (pin "5") (pinfunction "GND_5") (pintype "passive"))
      (node (ref "U16") (pin "5") (pinfunction "GND_5") (pintype "passive"))
      (node (ref "U16") (pin "6") (pinfunction "GND_6") (pintype "passive"))
      (node (ref "U16") (pin "7") (pinfunction "GND_7") (pintype "passive"))
      (node (ref "U16") (pin "8") (pinfunction "GND_8") (pintype "passive"))
      (node (ref "U2") (pin "5") (pinfunction "GND_5") (pintype "passive"))
      (node (ref "U2") (pin "6") (pinfunction "GND_6") (pintype "passive"))
      (node (ref "U2") (pin "7") (pinfunction "GND_7") (pintype "passive"))
      (node (ref "U2") (pin "8") (pinfunction "GND_8") (pintype "passive"))
      (node (ref "U3") (pin "5") (pinfunction "GND_5") (pintype "passive"))
      (node (ref "U3") (pin "6") (pinfunction "GND_6") (pintype "passive"))
      (node (ref "U3") (pin "7") (pinfunction "GND_7") (pintype "passive"))
      (node (ref "U3") (pin "8") (pinfunction "GND_8") (pintype "passive"))
      (node (ref "U4") (pin "15") (pinfunction "PGND_15") (pintype "passive"))
      (node (ref "U4") (pin "16") (pinfunction "PGND_16") (pintype "passive"))
      (node (ref "U4") (pin "17") (pinfunction "PAD_17") (pintype "passive"))
      (node (ref "U4") (pin "6") (pinfunction "AGND_6") (pintype "passive"))
      (node (ref "U4") (pin "8") (pinfunction "DEF_8") (pintype "passive"))
      (node (ref "U5") (pin "10") (pinfunction "A8_10") (pintype "passive"))
      (node (ref "U5") (pin "11") (pinfunction "GND_11") (pintype "passive"))
      (node (ref "U5") (pin "12") (pinfunction "GND_12") (pintype "passive"))
      (node (ref "U5") (pin "13") (pinfunction "GND_13") (pintype "passive"))
      (node (ref "U5") (pin "22") (pinfunction "~{OE}_22") (pintype "passive"))
      (node (ref "U5") (pin "9") (pinfunction "A7_9") (pintype "passive"))
      (node (ref "U6") (pin "5") (pinfunction "GND_5") (pintype "passive"))
      (node (ref "U6") (pin "8") (pinfunction "EN*_8") (pintype "passive"))
      (node (ref "U7") (pin "5") (pinfunction "GND_5") (pintype "passive"))
      (node (ref "U7") (pin "6") (pinfunction "DIN3_6") (pintype "passive"))
      (node (ref "U7") (pin "7") (pinfunction "DIN4_7") (pintype "passive"))
      (node (ref "U7") (pin "8") (pinfunction "EN*_8") (pintype "passive"))
      (node (ref "U8") (pin "11") (pinfunction "GND_11") (pintype "passive"))
      (node (ref "U8") (pin "12") (pinfunction "GND_12") (pintype "passive"))
      (node (ref "U8") (pin "13") (pinfunction "GND_13") (pintype "passive"))
      (node (ref "U8") (pin "14") (pinfunction "B8_14") (pintype "passive"))
      (node (ref "U8") (pin "15") (pinfunction "B7_15") (pintype "passive"))
      (node (ref "U8") (pin "16") (pinfunction "B6_16") (pintype "passive"))
      (node (ref "U8") (pin "17") (pinfunction "B5_17") (pintype "passive"))
      (node (ref "U8") (pin "18") (pinfunction "B4_18") (pintype "passive"))
      (node (ref "U8") (pin "19") (pinfunction "B3_19") (pintype "passive"))
      (node (ref "U8") (pin "2") (pinfunction "DIR_2") (pintype "passive"))
      (node (ref "U8") (pin "22") (pinfunction "~{OE}_22") (pintype "passive"))
      (node (ref "U9") (pin "9") (pinfunction "PAD_9") (pintype "passive"))
    )
    (net (code "43") (name "ISOGND1") (class "Default")
      (node (ref "J7") (pin "1") (pinfunction "1_1") (pintype "passive"))
      (node (ref "U15") (pin "2") (pinfunction "C1_2") (pintype "passive"))
      (node (ref "U15") (pin "3") (pinfunction "C2_3") (pintype "passive"))
    )
    (net (code "44") (name "Net-(J7-Pad2)") (class "Default")
      (node (ref "J7") (pin "2") (pinfunction "2_2") (pintype "passive"))
      (node (ref "R11") (pin "1") (pinfunction "1_1") (pintype "passive"))
    )
    (net (code "45") (name "Net-(J7-Pad3)") (class "Default")
      (node (ref "J7") (pin "3") (pinfunction "3_3") (pintype "passive"))
      (node (ref "R10") (pin "1") (pinfunction "1_1") (pintype "passive"))
    )
    (net (code "46") (name "Net-(L1-Pad1)") (class "Default")
      (node (ref "L1") (pin "1") (pinfunction "1_1") (pintype "passive"))
      (node (ref "U1") (pin "1") (pinfunction "SW_1") (pintype "passive"))
      (node (ref "U1") (pin "2") (pinfunction "SW_2") (pintype "passive"))
      (node (ref "U1") (pin "3") (pinfunction "SW_3") (pintype "passive"))
    )
    (net (code "47") (name "Net-(L2-Pad1)") (class "Default")
      (node (ref "L2") (pin "1") (pinfunction "1_1") (pintype "passive"))
      (node (ref "U4") (pin "1") (pinfunction "SW_1") (pintype "passive"))
      (node (ref "U4") (pin "2") (pinfunction "SW_2") (pintype "passive"))
      (node (ref "U4") (pin "3") (pinfunction "SW_3") (pintype "passive"))
    )
    (net (code "48") (name "Net-(LED1-Pad2)") (class "Default")
      (node (ref "LED1") (pin "2") (pinfunction "2_2") (pintype "passive"))
      (node (ref "R1") (pin "1") (pinfunction "1_1") (pintype "passive"))
    )
    (net (code "49") (name "Net-(Q2-PadG)") (class "Default")
      (node (ref "Q2") (pin "G") (pinfunction "G_G") (pintype "passive"))
      (node (ref "Q3") (pin "D") (pinfunction "D_D") (pintype "passive"))
      (node (ref "R9") (pin "1") (pinfunction "1_1") (pintype "passive"))
    )
    (net (code "50") (name "Net-(U1-FB)") (class "Default")
      (node (ref "R2") (pin "1") (pinfunction "1_1") (pintype "passive"))
      (node (ref "R4") (pin "2") (pinfunction "2_2") (pintype "passive"))
      (node (ref "U1") (pin "5") (pinfunction "FB_5") (pintype "passive"))
    )
    (net (code "51") (name "Net-(U1-PG)") (class "Default")
      (node (ref "R3") (pin "1") (pinfunction "1_1") (pintype "passive"))
      (node (ref "U1") (pin "4") (pinfunction "PG_4") (pintype "passive"))
    )
    (net (code "52") (name "Net-(U1-SS{slash}TR)") (class "Default")
      (node (ref "C6") (pin "1") (pinfunction "1_1") (pintype "passive"))
      (node (ref "U1") (pin "9") (pinfunction "SS/TR_9") (pintype "passive"))
    )
    (net (code "53") (name "Net-(U4-FB)") (class "Default")
      (node (ref "R5") (pin "1") (pinfunction "1_1") (pintype "passive"))
      (node (ref "R8") (pin "2") (pinfunction "2_2") (pintype "passive"))
      (node (ref "U4") (pin "5") (pinfunction "FB_5") (pintype "passive"))
    )
    (net (code "54") (name "Net-(U4-PG)") (class "Default")
      (node (ref "R6") (pin "1") (pinfunction "1_1") (pintype "passive"))
      (node (ref "U4") (pin "4") (pinfunction "PG_4") (pintype "passive"))
    )
    (net (code "55") (name "Net-(U4-SS{slash}TR)") (class "Default")
      (node (ref "C10") (pin "1") (pinfunction "1_1") (pintype "passive"))
      (node (ref "U4") (pin "9") (pinfunction "SS/TR_9") (pintype "passive"))
    )
    (net (code "56") (name "Net-(U15-A1)") (class "Default")
      (node (ref "R10") (pin "2") (pinfunction "2_2") (pintype "passive"))
      (node (ref "U15") (pin "1") (pinfunction "A1_1") (pintype "passive"))
    )
    (net (code "57") (name "Net-(U15-A2)") (class "Default")
      (node (ref "R11") (pin "2") (pinfunction "2_2") (pintype "passive"))
      (node (ref "U15") (pin "4") (pinfunction "A2_4") (pintype "passive"))
    )
    (net (code "58") (name "unconnected-(J2-Pad1)") (class "Default")
      (node (ref "J2") (pin "1") (pinfunction "1_1") (pintype "passive+no_connect"))
    )
    (net (code "59") (name "unconnected-(J2-Pad2)") (class "Default")
      (node (ref "J2") (pin "2") (pinfunction "2_2") (pintype "passive+no_connect"))
    )
    (net (code "60") (name "unconnected-(J2-Pad9)") (class "Default")
      (node (ref "J2") (pin "9") (pinfunction "9_9") (pintype "passive+no_connect"))
    )
    (net (code "61") (name "unconnected-(J2-Pad10)") (class "Default")
      (node (ref "J2") (pin "10") (pinfunction "10_10") (pintype "passive+no_connect"))
    )
    (net (code "62") (name "unconnected-(J3-Pad1)") (class "Default")
      (node (ref "J3") (pin "1") (pinfunction "1_1") (pintype "passive+no_connect"))
    )
    (net (code "63") (name "unconnected-(J3-Pad2)") (class "Default")
      (node (ref "J3") (pin "2") (pinfunction "2_2") (pintype "passive+no_connect"))
    )
    (net (code "64") (name "unconnected-(J3-Pad9)") (class "Default")
      (node (ref "J3") (pin "9") (pinfunction "9_9") (pintype "passive+no_connect"))
    )
    (net (code "65") (name "unconnected-(J3-Pad10)") (class "Default")
      (node (ref "J3") (pin "10") (pinfunction "10_10") (pintype "passive+no_connect"))
    )
    (net (code "66") (name "unconnected-(J4-Pad1)") (class "Default")
      (node (ref "J4") (pin "1") (pinfunction "1_1") (pintype "passive+no_connect"))
    )
    (net (code "67") (name "unconnected-(J4-Pad2)") (class "Default")
      (node (ref "J4") (pin "2") (pinfunction "2_2") (pintype "passive+no_connect"))
    )
    (net (code "68") (name "unconnected-(J4-Pad9)") (class "Default")
      (node (ref "J4") (pin "9") (pinfunction "9_9") (pintype "passive+no_connect"))
    )
    (net (code "69") (name "unconnected-(J4-Pad10)") (class "Default")
      (node (ref "J4") (pin "10") (pinfunction "10_10") (pintype "passive+no_connect"))
    )
    (net (code "70") (name "unconnected-(J5-Pad1)") (class "Default")
      (node (ref "J5") (pin "1") (pinfunction "1_1") (pintype "passive+no_connect"))
    )
    (net (code "71") (name "unconnected-(J5-Pad2)") (class "Default")
      (node (ref "J5") (pin "2") (pinfunction "2_2") (pintype "passive+no_connect"))
    )
    (net (code "72") (name "unconnected-(J5-Pad9)") (class "Default")
      (node (ref "J5") (pin "9") (pinfunction "9_9") (pintype "passive+no_connect"))
    )
    (net (code "73") (name "unconnected-(J5-Pad10)") (class "Default")
      (node (ref "J5") (pin "10") (pinfunction "10_10") (pintype "passive+no_connect"))
    )
    (net (code "74") (name "unconnected-(U5-B7-Pad15)") (class "Default")
      (node (ref "U5") (pin "15") (pinfunction "B7_15") (pintype "passive+no_connect"))
    )
    (net (code "75") (name "unconnected-(U5-B8-Pad14)") (class "Default")
      (node (ref "U5") (pin "14") (pinfunction "B8_14") (pintype "passive+no_connect"))
    )
    (net (code "76") (name "unconnected-(U7-DOUT3+-Pad11)") (class "Default")
      (node (ref "U7") (pin "11") (pinfunction "DOUT3+_11") (pintype "passive+no_connect"))
    )
    (net (code "77") (name "unconnected-(U7-DOUT3--Pad12)") (class "Default")
      (node (ref "U7") (pin "12") (pinfunction "DOUT3-_12") (pintype "passive+no_connect"))
    )
    (net (code "78") (name "unconnected-(U7-DOUT4+-Pad10)") (class "Default")
      (node (ref "U7") (pin "10") (pinfunction "DOUT4+_10") (pintype "passive+no_connect"))
    )
    (net (code "79") (name "unconnected-(U7-DOUT4--Pad9)") (class "Default")
      (node (ref "U7") (pin "9") (pinfunction "DOUT4-_9") (pintype "passive+no_connect"))
    )
  )
)
